# Radio_communication.net
KiCad netlist of a schematic drawn in Altium Designer
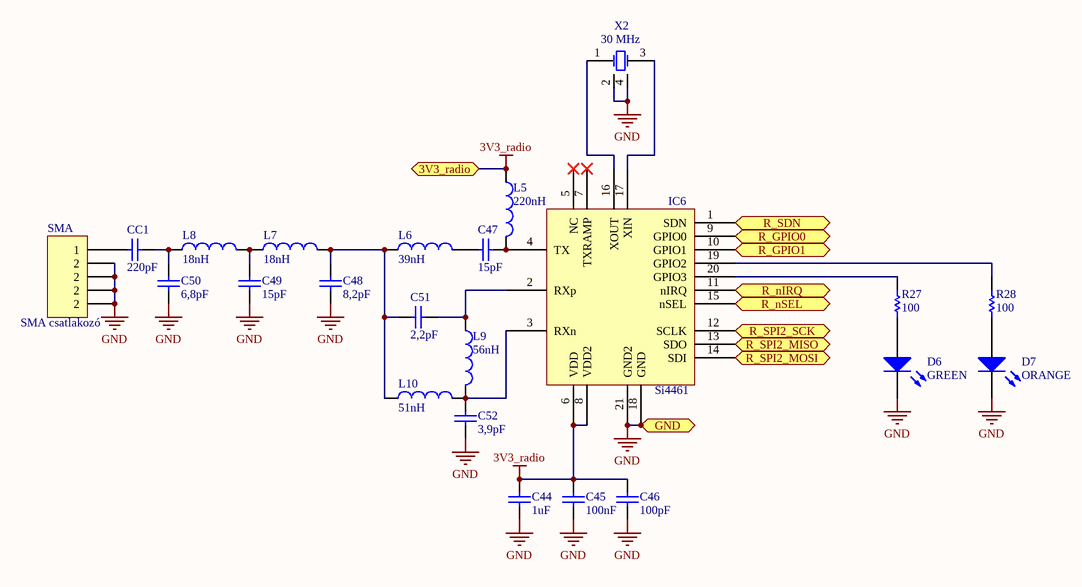
[diagram p0: Radio_communication.SchDoc]

(export (version "E")
  (design (tool "Eeschema 10.0.6"))
  (components
    (comp (ref "C44")
      (value "1uF")
      (footprint "FP_0603_CAP_080")
      (description "Capacitor")
      (fields (field (name "Comment") "Cap") (field (name "PUBLISHER") "Altium Limited"))
      (libsource (lib "Miscellaneous Devices") (part "Cap"))
    )
    (comp (ref "C45")
      (value "100nF")
      (footprint "FP_0603_CAP_080")
      (description "Capacitor")
      (fields (field (name "Comment") "Cap") (field (name "PUBLISHER") "Altium Limited"))
      (libsource (lib "Miscellaneous Devices") (part "Cap"))
    )
    (comp (ref "C46")
      (value "100pF")
      (footprint "FP_0603_CAP_080")
      (description "Capacitor")
      (fields (field (name "Comment") "Cap") (field (name "PUBLISHER") "Altium Limited"))
      (libsource (lib "Miscellaneous Devices") (part "Cap"))
    )
    (comp (ref "C47")
      (value "15pF")
      (footprint "FP_0603_CAP_080")
      (description "Capacitor")
      (fields (field (name "Comment") "Cap") (field (name "PUBLISHER") "Altium Limited"))
      (libsource (lib "Miscellaneous Devices") (part "Cap"))
    )
    (comp (ref "C48")
      (value "8,2pF")
      (footprint "FP_0603_CAP_080")
      (description "Capacitor")
      (fields (field (name "Comment") "Cap") (field (name "PUBLISHER") "Altium Limited"))
      (libsource (lib "Miscellaneous Devices") (part "Cap"))
    )
    (comp (ref "C49")
      (value "15pF")
      (footprint "FP_0603_CAP_080")
      (description "Capacitor")
      (fields (field (name "Comment") "Cap") (field (name "PUBLISHER") "Altium Limited"))
      (libsource (lib "Miscellaneous Devices") (part "Cap"))
    )
    (comp (ref "C50")
      (value "6,8pF")
      (footprint "FP_0603_CAP_080")
      (description "Capacitor")
      (fields (field (name "Comment") "Cap") (field (name "PUBLISHER") "Altium Limited"))
      (libsource (lib "Miscellaneous Devices") (part "Cap"))
    )
    (comp (ref "C51")
      (value "2,2pF")
      (footprint "FP_0603_CAP_080")
      (description "Capacitor")
      (fields (field (name "Comment") "Cap") (field (name "PUBLISHER") "Altium Limited"))
      (libsource (lib "Miscellaneous Devices") (part "Cap"))
    )
    (comp (ref "C52")
      (value "3,9pF")
      (footprint "FP_0603_CAP_080")
      (description "Capacitor")
      (fields (field (name "Comment") "Cap") (field (name "PUBLISHER") "Altium Limited"))
      (libsource (lib "Miscellaneous Devices") (part "Cap"))
    )
    (comp (ref "CC1")
      (value "220pF")
      (footprint "FP_0603_CAP_080")
      (description "Capacitor")
      (fields (field (name "Comment") "Cap") (field (name "PUBLISHER") "Altium Limited"))
      (libsource (lib "Miscellaneous Devices") (part "Cap"))
    )
    (comp (ref "D6")
      (value "GREEN")
      (footprint "FP_0805_LED_GREEN")
      (description "Typical RED GaAs LED")
      (libsource (lib "hallglib") (part "LED"))
    )
    (comp (ref "D7")
      (value "ORANGE")
      (footprint "FP_0805_LED_GREEN")
      (description "Typical RED GaAs LED")
      (libsource (lib "hallglib") (part "LED"))
    )
    (comp (ref "IC6")
      (value "Si4461")
      (footprint "QFN20_thermal_pad")
      (libsource (lib "diploma") (part "Si4461"))
    )
    (comp (ref "L5")
      (value "220nH")
      (footprint "FP_0603_CAP_080")
      (description "Inductor")
      (fields (field (name "PUBLISHER") "Altium Limited"))
      (libsource (lib "Miscellaneous Devices") (part "Inductor"))
    )
    (comp (ref "L6")
      (value "39nH")
      (footprint "FP_0603_CAP_080")
      (description "Inductor")
      (fields (field (name "PUBLISHER") "Altium Limited"))
      (libsource (lib "Miscellaneous Devices") (part "Inductor"))
    )
    (comp (ref "L7")
      (value "18nH")
      (footprint "FP_0603_CAP_080")
      (description "Inductor")
      (fields (field (name "PUBLISHER") "Altium Limited"))
      (libsource (lib "Miscellaneous Devices") (part "Inductor"))
    )
    (comp (ref "L8")
      (value "18nH")
      (footprint "FP_0603_CAP_080")
      (description "Inductor")
      (fields (field (name "PUBLISHER") "Altium Limited"))
      (libsource (lib "Miscellaneous Devices") (part "Inductor"))
    )
    (comp (ref "L9")
      (value "56nH")
      (footprint "FP_0603_CAP_080")
      (description "Inductor")
      (fields (field (name "PUBLISHER") "Altium Limited"))
      (libsource (lib "Miscellaneous Devices") (part "Inductor"))
    )
    (comp (ref "L10")
      (value "51nH")
      (footprint "FP_0603_CAP_080")
      (description "Inductor")
      (fields (field (name "PUBLISHER") "Altium Limited"))
      (libsource (lib "Miscellaneous Devices") (part "Inductor"))
    )
    (comp (ref "R27")
      (value "100")
      (footprint "FP_0603_RES")
      (description "Resistor")
      (fields (field (name "Comment") "Res1") (field (name "PUBLISHER") "Altium Limited"))
      (libsource (lib "Miscellaneous Devices") (part "Res1"))
    )
    (comp (ref "R28")
      (value "100")
      (footprint "FP_0603_RES")
      (description "Resistor")
      (fields (field (name "Comment") "Res1") (field (name "PUBLISHER") "Altium Limited"))
      (libsource (lib "Miscellaneous Devices") (part "Res1"))
    )
    (comp (ref "SMA")
      (value "SMA csatlakozó")
      (footprint "SMA_connector")
      (description "Header, 5-Pin")
      (fields (field (name "PUBLISHER") "Altium Limited"))
      (libsource (lib "Miscellaneous Connectors") (part "Header 5"))
    )
    (comp (ref "X2")
      (value "30 MHz")
      (footprint "crystal_sx2520")
      (description "Crystal Oscillator")
      (fields (field (name "PUBLISHER") "Altium Limited"))
      (libsource (lib "Miscellaneous Devices") (part "XTAL"))
    )
  )
  (nets
    (net (code "1") (name "/R_GPIO0") (class "Default")
      (node (ref "IC6") (pin "9") (pinfunction "GPIO0_9") (pintype "passive"))
    )
    (net (code "2") (name "/R_GPIO1") (class "Default")
      (node (ref "IC6") (pin "10") (pinfunction "GPIO1_10") (pintype "passive"))
    )
    (net (code "3") (name "/R_SDN") (class "Default")
      (node (ref "IC6") (pin "1") (pinfunction "SDN_1") (pintype "passive"))
    )
    (net (code "4") (name "/R_SPI2_MISO") (class "Default")
      (node (ref "IC6") (pin "13") (pinfunction "SDO_13") (pintype "passive"))
    )
    (net (code "5") (name "/R_SPI2_MOSI") (class "Default")
      (node (ref "IC6") (pin "14") (pinfunction "SDI_14") (pintype "passive"))
    )
    (net (code "6") (name "/R_SPI2_SCK") (class "Default")
      (node (ref "IC6") (pin "12") (pinfunction "SCLK_12") (pintype "passive"))
    )
    (net (code "7") (name "/R_nIRQ") (class "Default")
      (node (ref "IC6") (pin "11") (pinfunction "nIRQ_11") (pintype "passive"))
    )
    (net (code "8") (name "/R_nSEL") (class "Default")
      (node (ref "IC6") (pin "15") (pinfunction "nSEL_15") (pintype "passive"))
    )
    (net (code "9") (name "3V3_radio") (class "Default")
      (node (ref "C44") (pin "2") (pinfunction "2_2") (pintype "passive"))
      (node (ref "C45") (pin "2") (pinfunction "2_2") (pintype "passive"))
      (node (ref "C46") (pin "2") (pinfunction "2_2") (pintype "passive"))
      (node (ref "IC6") (pin "6") (pinfunction "VDD_6") (pintype "passive"))
      (node (ref "IC6") (pin "8") (pinfunction "VDD2_8") (pintype "passive"))
      (node (ref "L5") (pin "1") (pinfunction "1_1") (pintype "passive"))
    )
    (net (code "10") (name "GND") (class "Default")
      (node (ref "C44") (pin "1") (pinfunction "1_1") (pintype "passive"))
      (node (ref "C45") (pin "1") (pinfunction "1_1") (pintype "passive"))
      (node (ref "C46") (pin "1") (pinfunction "1_1") (pintype "passive"))
      (node (ref "C48") (pin "2") (pinfunction "2_2") (pintype "passive"))
      (node (ref "C49") (pin "2") (pinfunction "2_2") (pintype "passive"))
      (node (ref "C50") (pin "2") (pinfunction "2_2") (pintype "passive"))
      (node (ref "C52") (pin "1") (pinfunction "1_1") (pintype "passive"))
      (node (ref "D6") (pin "2") (pinfunction "K_2") (pintype "passive"))
      (node (ref "D7") (pin "2") (pinfunction "K_2") (pintype "passive"))
      (node (ref "IC6") (pin "18") (pinfunction "GND_18") (pintype "passive"))
      (node (ref "IC6") (pin "21") (pinfunction "GND2_21") (pintype "passive"))
      (node (ref "SMA") (pin "2") (pinfunction "2_2") (pintype "passive"))
      (node (ref "X2") (pin "2") (pinfunction "OSC2_2") (pintype "passive"))
      (node (ref "X2") (pin "4") (pinfunction "4_4") (pintype "passive"))
    )
    (net (code "11") (name "Net-(C47-Pad2)") (class "Default")
      (node (ref "C47") (pin "2") (pinfunction "2_2") (pintype "passive"))
      (node (ref "L6") (pin "2") (pinfunction "2_2") (pintype "passive"))
    )
    (net (code "12") (name "Net-(C48-Pad1)") (class "Default")
      (node (ref "C48") (pin "1") (pinfunction "1_1") (pintype "passive"))
      (node (ref "C51") (pin "1") (pinfunction "1_1") (pintype "passive"))
      (node (ref "L10") (pin "1") (pinfunction "1_1") (pintype "passive"))
      (node (ref "L6") (pin "1") (pinfunction "1_1") (pintype "passive"))
      (node (ref "L7") (pin "2") (pinfunction "2_2") (pintype "passive"))
    )
    (net (code "13") (name "Net-(C49-Pad1)") (class "Default")
      (node (ref "C49") (pin "1") (pinfunction "1_1") (pintype "passive"))
      (node (ref "L7") (pin "1") (pinfunction "1_1") (pintype "passive"))
      (node (ref "L8") (pin "2") (pinfunction "2_2") (pintype "passive"))
    )
    (net (code "14") (name "Net-(C50-Pad1)") (class "Default")
      (node (ref "C50") (pin "1") (pinfunction "1_1") (pintype "passive"))
      (node (ref "CC1") (pin "2") (pinfunction "2_2") (pintype "passive"))
      (node (ref "L8") (pin "1") (pinfunction "1_1") (pintype "passive"))
    )
    (net (code "15") (name "Net-(CC1-Pad1)") (class "Default")
      (node (ref "CC1") (pin "1") (pinfunction "1_1") (pintype "passive"))
      (node (ref "SMA") (pin "1") (pinfunction "1_1") (pintype "passive"))
    )
    (net (code "16") (name "Net-(D6-A)") (class "Default")
      (node (ref "D6") (pin "1") (pinfunction "A_1") (pintype "passive"))
      (node (ref "R27") (pin "1") (pinfunction "1_1") (pintype "passive"))
    )
    (net (code "17") (name "Net-(D7-A)") (class "Default")
      (node (ref "D7") (pin "1") (pinfunction "A_1") (pintype "passive"))
      (node (ref "R28") (pin "1") (pinfunction "1_1") (pintype "passive"))
    )
    (net (code "18") (name "Net-(IC6-GPIO2)") (class "Default")
      (node (ref "IC6") (pin "19") (pinfunction "GPIO2_19") (pintype "passive"))
      (node (ref "R28") (pin "2") (pinfunction "2_2") (pintype "passive"))
    )
    (net (code "19") (name "Net-(IC6-GPIO3)") (class "Default")
      (node (ref "IC6") (pin "20") (pinfunction "GPIO3_20") (pintype "passive"))
      (node (ref "R27") (pin "2") (pinfunction "2_2") (pintype "passive"))
    )
    (net (code "20") (name "Net-(IC6-RXn)") (class "Default")
      (node (ref "C52") (pin "2") (pinfunction "2_2") (pintype "passive"))
      (node (ref "IC6") (pin "3") (pinfunction "RXn_3") (pintype "passive"))
      (node (ref "L10") (pin "2") (pinfunction "2_2") (pintype "passive"))
      (node (ref "L9") (pin "2") (pinfunction "2_2") (pintype "passive"))
    )
    (net (code "21") (name "Net-(IC6-RXp)") (class "Default")
      (node (ref "C51") (pin "2") (pinfunction "2_2") (pintype "passive"))
      (node (ref "IC6") (pin "2") (pinfunction "RXp_2") (pintype "passive"))
      (node (ref "L9") (pin "1") (pinfunction "1_1") (pintype "passive"))
    )
    (net (code "22") (name "Net-(IC6-TX)") (class "Default")
      (node (ref "C47") (pin "1") (pinfunction "1_1") (pintype "passive"))
      (node (ref "IC6") (pin "4") (pinfunction "TX_4") (pintype "passive"))
      (node (ref "L5") (pin "2") (pinfunction "2_2") (pintype "passive"))
    )
    (net (code "23") (name "Net-(IC6-XIN)") (class "Default")
      (node (ref "IC6") (pin "17") (pinfunction "XIN_17") (pintype "passive"))
      (node (ref "X2") (pin "3") (pinfunction "3_3") (pintype "passive"))
    )
    (net (code "24") (name "Net-(IC6-XOUT)") (class "Default")
      (node (ref "IC6") (pin "16") (pinfunction "XOUT_16") (pintype "passive"))
      (node (ref "X2") (pin "1") (pinfunction "OSC1_1") (pintype "passive"))
    )
    (net (code "25") (name "unconnected-(IC6-NC-Pad5)") (class "Default")
      (node (ref "IC6") (pin "5") (pinfunction "NC_5") (pintype "passive+no_connect"))
    )
    (net (code "26") (name "unconnected-(IC6-TXRAMP-Pad7)") (class "Default")
      (node (ref "IC6") (pin "7") (pinfunction "TXRAMP_7") (pintype "passive+no_connect"))
    )
  )
)
